# 02_-_DISPLAY.net
KiCad netlist of a schematic drawn in Altium Designer
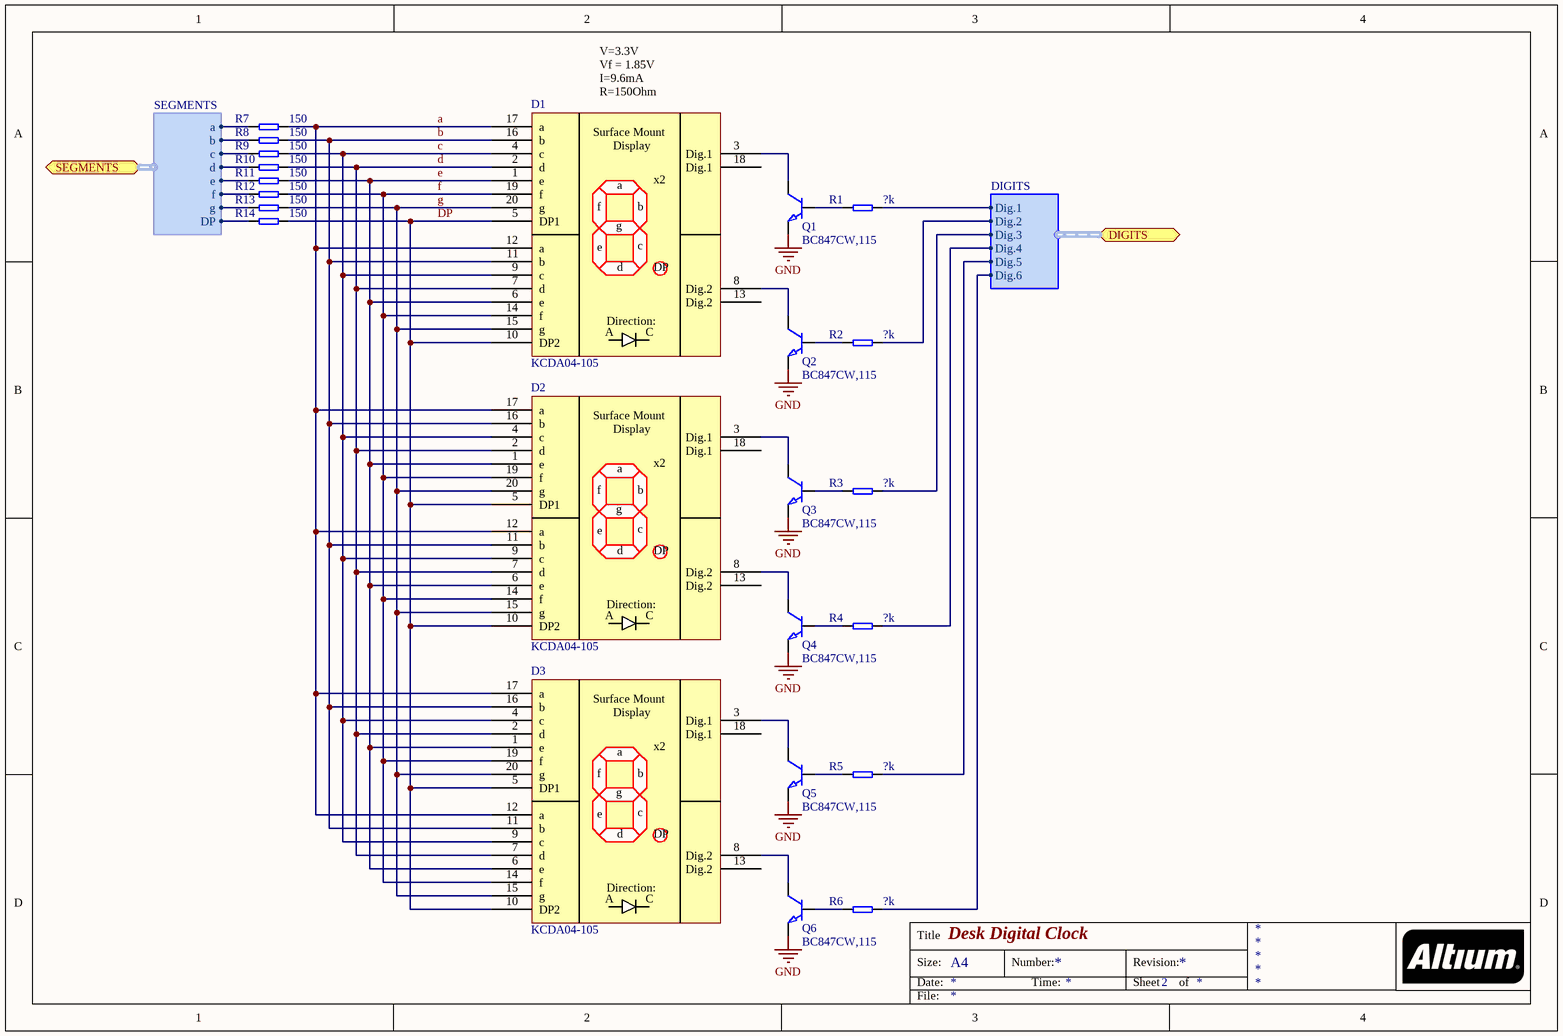
[diagram p0: [02] - DISPLAY.SchDoc]

(export (version "E")
  (design (tool "Eeschema 10.0.6"))
  (components
    (comp (ref "D1")
      (value "KCDA04-105")
      (description "Surface Mount Display")
      (fields (field (name "MANUFACTURER") "Kingbright"))
      (libsource (lib "1") (part "KCDA04-105"))
    )
    (comp (ref "D2")
      (value "KCDA04-105")
      (description "Surface Mount Display")
      (fields (field (name "MANUFACTURER") "Kingbright"))
      (libsource (lib "1") (part "KCDA04-105"))
    )
    (comp (ref "D3")
      (value "KCDA04-105")
      (description "Surface Mount Display")
      (fields (field (name "MANUFACTURER") "Kingbright"))
      (libsource (lib "1") (part "KCDA04-105"))
    )
    (comp (ref "Q1")
      (value "BC847CW,115")
      (description "TRANS NPN 45V 0.1A SOT23")
      (fields (field (name "MANUFACTURER") "Nexperia USA Inc."))
      (libsource (lib "1") (part "BC847CW,115"))
    )
    (comp (ref "Q2")
      (value "BC847CW,115")
      (description "TRANS NPN 45V 0.1A SOT23")
      (fields (field (name "MANUFACTURER") "Nexperia USA Inc."))
      (libsource (lib "1") (part "BC847CW,115"))
    )
    (comp (ref "Q3")
      (value "BC847CW,115")
      (description "TRANS NPN 45V 0.1A SOT23")
      (fields (field (name "MANUFACTURER") "Nexperia USA Inc."))
      (libsource (lib "1") (part "BC847CW,115"))
    )
    (comp (ref "Q4")
      (value "BC847CW,115")
      (description "TRANS NPN 45V 0.1A SOT23")
      (fields (field (name "MANUFACTURER") "Nexperia USA Inc."))
      (libsource (lib "1") (part "BC847CW,115"))
    )
    (comp (ref "Q5")
      (value "BC847CW,115")
      (description "TRANS NPN 45V 0.1A SOT23")
      (fields (field (name "MANUFACTURER") "Nexperia USA Inc."))
      (libsource (lib "1") (part "BC847CW,115"))
    )
    (comp (ref "Q6")
      (value "BC847CW,115")
      (description "TRANS NPN 45V 0.1A SOT23")
      (fields (field (name "MANUFACTURER") "Nexperia USA Inc."))
      (libsource (lib "1") (part "BC847CW,115"))
    )
    (comp (ref "R1") (value "?k") (description "RESISTOR") (libsource (lib "1") (part "Res")))
    (comp (ref "R2") (value "?k") (description "RESISTOR") (libsource (lib "1") (part "Res")))
    (comp (ref "R3") (value "?k") (description "RESISTOR") (libsource (lib "1") (part "Res")))
    (comp (ref "R4") (value "?k") (description "RESISTOR") (libsource (lib "1") (part "Res")))
    (comp (ref "R5") (value "?k") (description "RESISTOR") (libsource (lib "1") (part "Res")))
    (comp (ref "R6") (value "?k") (description "RESISTOR") (libsource (lib "1") (part "Res")))
    (comp (ref "R7") (value "150") (description "RESISTOR") (libsource (lib "1") (part "Res")))
    (comp (ref "R8") (value "150") (description "RESISTOR") (libsource (lib "1") (part "Res")))
    (comp (ref "R9") (value "150") (description "RESISTOR") (libsource (lib "1") (part "Res")))
    (comp (ref "R10") (value "150") (description "RESISTOR") (libsource (lib "1") (part "Res")))
    (comp (ref "R11") (value "150") (description "RESISTOR") (libsource (lib "1") (part "Res")))
    (comp (ref "R12") (value "150") (description "RESISTOR") (libsource (lib "1") (part "Res")))
    (comp (ref "R13") (value "150") (description "RESISTOR") (libsource (lib "1") (part "Res")))
    (comp (ref "R14") (value "150") (description "RESISTOR") (libsource (lib "1") (part "Res")))
  )
  (nets
    (net (code "3") (name "/DP") (class "Default")
      (node (ref "D1") (pin "10") (pinfunction "DP2_10") (pintype "passive"))
      (node (ref "D1") (pin "5") (pinfunction "DP1_5") (pintype "passive"))
      (node (ref "D2") (pin "10") (pinfunction "DP2_10") (pintype "passive"))
      (node (ref "D2") (pin "5") (pinfunction "DP1_5") (pintype "passive"))
      (node (ref "D3") (pin "10") (pinfunction "DP2_10") (pintype "passive"))
      (node (ref "D3") (pin "5") (pinfunction "DP1_5") (pintype "passive"))
      (node (ref "R14") (pin "2") (pinfunction "2_2") (pintype "passive"))
    )
    (net (code "4") (name "/Dig.1") (class "Default")
      (node (ref "R1") (pin "2") (pinfunction "2_2") (pintype "passive"))
    )
    (net (code "5") (name "/Dig.2") (class "Default")
      (node (ref "R2") (pin "2") (pinfunction "2_2") (pintype "passive"))
    )
    (net (code "6") (name "/Dig.3") (class "Default")
      (node (ref "R3") (pin "2") (pinfunction "2_2") (pintype "passive"))
    )
    (net (code "7") (name "/Dig.4") (class "Default")
      (node (ref "R4") (pin "2") (pinfunction "2_2") (pintype "passive"))
    )
    (net (code "8") (name "/Dig.5") (class "Default")
      (node (ref "R5") (pin "2") (pinfunction "2_2") (pintype "passive"))
    )
    (net (code "9") (name "/Dig.6") (class "Default")
      (node (ref "R6") (pin "2") (pinfunction "2_2") (pintype "passive"))
    )
    (net (code "10") (name "/a") (class "Default")
      (node (ref "D1") (pin "12") (pinfunction "a_12") (pintype "passive"))
      (node (ref "D1") (pin "17") (pinfunction "a_17") (pintype "passive"))
      (node (ref "D2") (pin "12") (pinfunction "a_12") (pintype "passive"))
      (node (ref "D2") (pin "17") (pinfunction "a_17") (pintype "passive"))
      (node (ref "D3") (pin "12") (pinfunction "a_12") (pintype "passive"))
      (node (ref "D3") (pin "17") (pinfunction "a_17") (pintype "passive"))
      (node (ref "R7") (pin "2") (pinfunction "2_2") (pintype "passive"))
    )
    (net (code "11") (name "/b") (class "Default")
      (node (ref "D1") (pin "11") (pinfunction "b_11") (pintype "passive"))
      (node (ref "D1") (pin "16") (pinfunction "b_16") (pintype "passive"))
      (node (ref "D2") (pin "11") (pinfunction "b_11") (pintype "passive"))
      (node (ref "D2") (pin "16") (pinfunction "b_16") (pintype "passive"))
      (node (ref "D3") (pin "11") (pinfunction "b_11") (pintype "passive"))
      (node (ref "D3") (pin "16") (pinfunction "b_16") (pintype "passive"))
      (node (ref "R8") (pin "2") (pinfunction "2_2") (pintype "passive"))
    )
    (net (code "12") (name "/c") (class "Default")
      (node (ref "D1") (pin "4") (pinfunction "c_4") (pintype "passive"))
      (node (ref "D1") (pin "9") (pinfunction "c_9") (pintype "passive"))
      (node (ref "D2") (pin "4") (pinfunction "c_4") (pintype "passive"))
      (node (ref "D2") (pin "9") (pinfunction "c_9") (pintype "passive"))
      (node (ref "D3") (pin "4") (pinfunction "c_4") (pintype "passive"))
      (node (ref "D3") (pin "9") (pinfunction "c_9") (pintype "passive"))
      (node (ref "R9") (pin "2") (pinfunction "2_2") (pintype "passive"))
    )
    (net (code "13") (name "/d") (class "Default")
      (node (ref "D1") (pin "2") (pinfunction "d_2") (pintype "passive"))
      (node (ref "D1") (pin "7") (pinfunction "d_7") (pintype "passive"))
      (node (ref "D2") (pin "2") (pinfunction "d_2") (pintype "passive"))
      (node (ref "D2") (pin "7") (pinfunction "d_7") (pintype "passive"))
      (node (ref "D3") (pin "2") (pinfunction "d_2") (pintype "passive"))
      (node (ref "D3") (pin "7") (pinfunction "d_7") (pintype "passive"))
      (node (ref "R10") (pin "2") (pinfunction "2_2") (pintype "passive"))
    )
    (net (code "14") (name "/e") (class "Default")
      (node (ref "D1") (pin "1") (pinfunction "e_1") (pintype "passive"))
      (node (ref "D1") (pin "6") (pinfunction "e_6") (pintype "passive"))
      (node (ref "D2") (pin "1") (pinfunction "e_1") (pintype "passive"))
      (node (ref "D2") (pin "6") (pinfunction "e_6") (pintype "passive"))
      (node (ref "D3") (pin "1") (pinfunction "e_1") (pintype "passive"))
      (node (ref "D3") (pin "6") (pinfunction "e_6") (pintype "passive"))
      (node (ref "R11") (pin "2") (pinfunction "2_2") (pintype "passive"))
    )
    (net (code "15") (name "/f") (class "Default")
      (node (ref "D1") (pin "14") (pinfunction "f_14") (pintype "passive"))
      (node (ref "D1") (pin "19") (pinfunction "f_19") (pintype "passive"))
      (node (ref "D2") (pin "14") (pinfunction "f_14") (pintype "passive"))
      (node (ref "D2") (pin "19") (pinfunction "f_19") (pintype "passive"))
      (node (ref "D3") (pin "14") (pinfunction "f_14") (pintype "passive"))
      (node (ref "D3") (pin "19") (pinfunction "f_19") (pintype "passive"))
      (node (ref "R12") (pin "2") (pinfunction "2_2") (pintype "passive"))
    )
    (net (code "16") (name "/g") (class "Default")
      (node (ref "D1") (pin "15") (pinfunction "g_15") (pintype "passive"))
      (node (ref "D1") (pin "20") (pinfunction "g_20") (pintype "passive"))
      (node (ref "D2") (pin "15") (pinfunction "g_15") (pintype "passive"))
      (node (ref "D2") (pin "20") (pinfunction "g_20") (pintype "passive"))
      (node (ref "D3") (pin "15") (pinfunction "g_15") (pintype "passive"))
      (node (ref "D3") (pin "20") (pinfunction "g_20") (pintype "passive"))
      (node (ref "R13") (pin "2") (pinfunction "2_2") (pintype "passive"))
    )
    (net (code "19") (name "GND") (class "Default")
      (node (ref "Q1") (pin "E") (pinfunction "E_E") (pintype "passive"))
      (node (ref "Q2") (pin "E") (pinfunction "E_E") (pintype "passive"))
      (node (ref "Q3") (pin "E") (pinfunction "E_E") (pintype "passive"))
      (node (ref "Q4") (pin "E") (pinfunction "E_E") (pintype "passive"))
      (node (ref "Q5") (pin "E") (pinfunction "E_E") (pintype "passive"))
      (node (ref "Q6") (pin "E") (pinfunction "E_E") (pintype "passive"))
    )
    (net (code "20") (name "Net-(D1-Dig.1-Pad3)") (class "Default")
      (node (ref "D1") (pin "3") (pinfunction "Dig.1_3") (pintype "passive"))
      (node (ref "Q1") (pin "C") (pinfunction "C_C") (pintype "passive"))
    )
    (net (code "21") (name "Net-(D1-Dig.2-Pad8)") (class "Default")
      (node (ref "D1") (pin "8") (pinfunction "Dig.2_8") (pintype "passive"))
      (node (ref "Q2") (pin "C") (pinfunction "C_C") (pintype "passive"))
    )
    (net (code "22") (name "Net-(D2-Dig.1-Pad3)") (class "Default")
      (node (ref "D2") (pin "3") (pinfunction "Dig.1_3") (pintype "passive"))
      (node (ref "Q3") (pin "C") (pinfunction "C_C") (pintype "passive"))
    )
    (net (code "23") (name "Net-(D2-Dig.2-Pad8)") (class "Default")
      (node (ref "D2") (pin "8") (pinfunction "Dig.2_8") (pintype "passive"))
      (node (ref "Q4") (pin "C") (pinfunction "C_C") (pintype "passive"))
    )
    (net (code "24") (name "Net-(D3-Dig.1-Pad3)") (class "Default")
      (node (ref "D3") (pin "3") (pinfunction "Dig.1_3") (pintype "passive"))
      (node (ref "Q5") (pin "C") (pinfunction "C_C") (pintype "passive"))
    )
    (net (code "25") (name "Net-(D3-Dig.2-Pad8)") (class "Default")
      (node (ref "D3") (pin "8") (pinfunction "Dig.2_8") (pintype "passive"))
      (node (ref "Q6") (pin "C") (pinfunction "C_C") (pintype "passive"))
    )
    (net (code "26") (name "Net-(Q1-PadB)") (class "Default")
      (node (ref "Q1") (pin "B") (pinfunction "B_B") (pintype "passive"))
      (node (ref "R1") (pin "1") (pinfunction "1_1") (pintype "passive"))
    )
    (net (code "27") (name "Net-(Q2-PadB)") (class "Default")
      (node (ref "Q2") (pin "B") (pinfunction "B_B") (pintype "passive"))
      (node (ref "R2") (pin "1") (pinfunction "1_1") (pintype "passive"))
    )
    (net (code "28") (name "Net-(Q3-PadB)") (class "Default")
      (node (ref "Q3") (pin "B") (pinfunction "B_B") (pintype "passive"))
      (node (ref "R3") (pin "1") (pinfunction "1_1") (pintype "passive"))
    )
    (net (code "29") (name "Net-(Q4-PadB)") (class "Default")
      (node (ref "Q4") (pin "B") (pinfunction "B_B") (pintype "passive"))
      (node (ref "R4") (pin "1") (pinfunction "1_1") (pintype "passive"))
    )
    (net (code "30") (name "Net-(Q5-PadB)") (class "Default")
      (node (ref "Q5") (pin "B") (pinfunction "B_B") (pintype "passive"))
      (node (ref "R5") (pin "1") (pinfunction "1_1") (pintype "passive"))
    )
    (net (code "31") (name "Net-(Q6-PadB)") (class "Default")
      (node (ref "Q6") (pin "B") (pinfunction "B_B") (pintype "passive"))
      (node (ref "R6") (pin "1") (pinfunction "1_1") (pintype "passive"))
    )
    (net (code "32") (name "unconnected-(D1-Dig.1-Pad18)") (class "Default")
      (node (ref "D1") (pin "18") (pinfunction "Dig.1_18") (pintype "passive"))
    )
    (net (code "33") (name "unconnected-(D1-Dig.2-Pad13)") (class "Default")
      (node (ref "D1") (pin "13") (pinfunction "Dig.2_13") (pintype "passive"))
    )
    (net (code "34") (name "unconnected-(D2-Dig.1-Pad18)") (class "Default")
      (node (ref "D2") (pin "18") (pinfunction "Dig.1_18") (pintype "passive"))
    )
    (net (code "35") (name "unconnected-(D2-Dig.2-Pad13)") (class "Default")
      (node (ref "D2") (pin "13") (pinfunction "Dig.2_13") (pintype "passive"))
    )
    (net (code "36") (name "unconnected-(D3-Dig.1-Pad18)") (class "Default")
      (node (ref "D3") (pin "18") (pinfunction "Dig.1_18") (pintype "passive"))
    )
    (net (code "37") (name "unconnected-(D3-Dig.2-Pad13)") (class "Default")
      (node (ref "D3") (pin "13") (pinfunction "Dig.2_13") (pintype "passive"))
    )
    (net (code "38") (name "unconnected-(R7-Pad1)") (class "Default")
      (node (ref "R7") (pin "1") (pinfunction "1_1") (pintype "passive"))
    )
    (net (code "39") (name "unconnected-(R8-Pad1)") (class "Default")
      (node (ref "R8") (pin "1") (pinfunction "1_1") (pintype "passive"))
    )
    (net (code "40") (name "unconnected-(R9-Pad1)") (class "Default")
      (node (ref "R9") (pin "1") (pinfunction "1_1") (pintype "passive"))
    )
    (net (code "41") (name "unconnected-(R10-Pad1)") (class "Default")
      (node (ref "R10") (pin "1") (pinfunction "1_1") (pintype "passive"))
    )
    (net (code "42") (name "unconnected-(R11-Pad1)") (class "Default")
      (node (ref "R11") (pin "1") (pinfunction "1_1") (pintype "passive"))
    )
    (net (code "43") (name "unconnected-(R12-Pad1)") (class "Default")
      (node (ref "R12") (pin "1") (pinfunction "1_1") (pintype "passive"))
    )
    (net (code "44") (name "unconnected-(R13-Pad1)") (class "Default")
      (node (ref "R13") (pin "1") (pinfunction "1_1") (pintype "passive"))
    )
    (net (code "45") (name "unconnected-(R14-Pad1)") (class "Default")
      (node (ref "R14") (pin "1") (pinfunction "1_1") (pintype "passive"))
    )
  )
)
